# SENSADO.net
KiCad netlist of a schematic drawn in Altium Designer
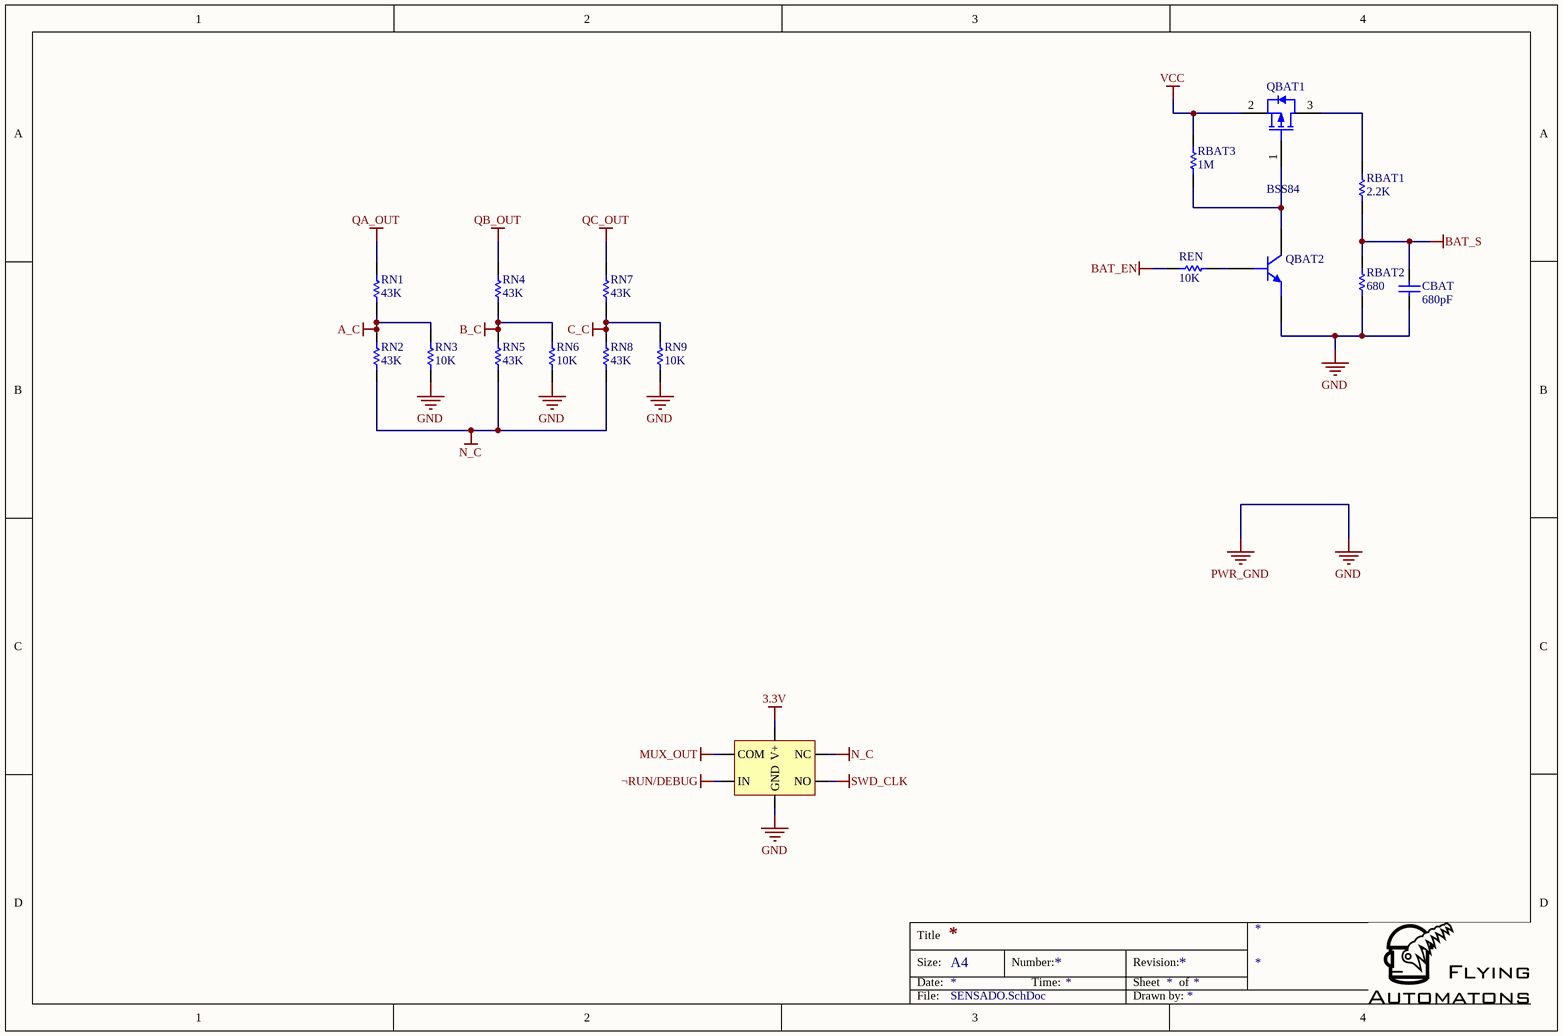
[diagram p0: SENSADO.SchDoc]

(export (version "E")
  (design (tool "Eeschema 10.0.6"))
  (components
    (comp (ref "CBAT")
      (value "680pF")
      (footprint "CAPC1608L")
      (description "CAP CER 680PF 50V 5% NP0 0603")
      (fields
        (field (name "MANUFACTURER") "Samsung Electro-Mechanics America, Inc")
        (field (name "MANUFACTURER PART NUMBER") "CL10C681JB8NFNC")
      )
      (libsource (lib "Passive#csv") (part "CAP_680p_0603_50V_NP0_5%"))
    )
    (comp (ref "mux")
      (value "TS5A3159A")
      (footprint "JEDEC_MO-178AB")
      (description "IC SWITCH SPDT SOT23-6")
      (fields
        (field (name "MANUFACTURER") "\"Texas Instruments\"")
        (field (name "MANUFACTURER PART NUMBER") "TS5A3159ADBVR")
      )
      (libsource (lib "Analog_IC#csv") (part "x-TI_TS5A3159A"))
    )
    (comp (ref "QBAT1")
      (value "BSS84")
      (footprint "SOT23-3L")
      (description "MOSFET P-CH 50V 130MA SOT-23")
      (fields (field (name "MANUFACTURER") "Fairchild Semiconductor"))
      (libsource (lib "Discrete#csv") (part "BSS84"))
    )
    (comp (ref "QBAT2")
      (value "BJT-NPN-BEC")
      (footprint "SOT23-3L")
      (description "TRANSISTOR NPN 40V 0.2A SOT23")
      (fields
        (field (name "MANUFACTURER") "NXP Semiconductors")
        (field (name "MANUFACTURER PART NUMBER") "MMBT3904")
      )
      (libsource (lib "Discrete#csv") (part "MMBT3904"))
    )
    (comp (ref "RBAT1")
      (value "2.2K")
      (footprint "RESC1608L")
      (description "RES 2.2K OHM 1/10W 1% 0603 SMD")
      (fields
        (field (name "MANUFACTURER") "Rohm Semiconductor")
        (field (name "MANUFACTURER PART NUMBER") "MCR03ERTF2201")
      )
      (libsource (lib "Passive#csv") (part "RES_2K2_0603_0W1_1%"))
    )
    (comp (ref "RBAT2")
      (value "680")
      (footprint "RESC1608L")
      (description "RES 680 OHM 1/10W 1% 0603 SMD")
      (fields
        (field (name "MANUFACTURER") "Rohm Semiconductor")
        (field (name "MANUFACTURER PART NUMBER") "MCR03ERTF6800")
      )
      (libsource (lib "Passive#csv") (part "RES_680_0603_0W1_1%"))
    )
    (comp (ref "RBAT3")
      (value "1M")
      (footprint "RESC1608L")
      (description "RES 1.00M OHM 1/10W 1% 0603 SMD")
      (fields
        (field (name "MANUFACTURER") "Yageo")
        (field (name "MANUFACTURER PART NUMBER") "RC0603FR-071ML")
      )
      (libsource (lib "Passive#csv") (part "RES_1M_0603_0W1_1%"))
    )
    (comp (ref "REN")
      (value "10K")
      (footprint "RESC1608L")
      (description "RES 10K OHM 1/10W 5% 0603")
      (fields (field (name "MANUFACTURER PART NUMBER") "RC1608J103CS"))
      (libsource (lib "Passive#csv") (part "RES_10K_0603_0W1_1%"))
    )
    (comp (ref "RN1")
      (value "43K")
      (footprint "RESC1608L")
      (description "RES 10K OHM 1/10W 5% 0603")
      (fields (field (name "MANUFACTURER PART NUMBER") "RC1608J103CS"))
      (libsource (lib "Passive#csv") (part "RES_10K_0603_0W1_1%"))
    )
    (comp (ref "RN2")
      (value "43K")
      (footprint "RESC1608L")
      (description "RES 10K OHM 1/10W 5% 0603")
      (fields (field (name "MANUFACTURER PART NUMBER") "RC1608J103CS"))
      (libsource (lib "Passive#csv") (part "RES_10K_0603_0W1_1%"))
    )
    (comp (ref "RN3")
      (value "10K")
      (footprint "RESC1608L")
      (description "RES 10K OHM 1/10W 5% 0603")
      (fields (field (name "MANUFACTURER PART NUMBER") "RC1608J103CS"))
      (libsource (lib "Passive#csv") (part "RES_10K_0603_0W1_1%"))
    )
    (comp (ref "RN4")
      (value "43K")
      (footprint "RESC1608L")
      (description "RES 10K OHM 1/10W 5% 0603")
      (fields (field (name "MANUFACTURER PART NUMBER") "RC1608J103CS"))
      (libsource (lib "Passive#csv") (part "RES_10K_0603_0W1_1%"))
    )
    (comp (ref "RN5")
      (value "43K")
      (footprint "RESC1608L")
      (description "RES 10K OHM 1/10W 5% 0603")
      (fields (field (name "MANUFACTURER PART NUMBER") "RC1608J103CS"))
      (libsource (lib "Passive#csv") (part "RES_10K_0603_0W1_1%"))
    )
    (comp (ref "RN6")
      (value "10K")
      (footprint "RESC1608L")
      (description "RES 10K OHM 1/10W 5% 0603")
      (fields (field (name "MANUFACTURER PART NUMBER") "RC1608J103CS"))
      (libsource (lib "Passive#csv") (part "RES_10K_0603_0W1_1%"))
    )
    (comp (ref "RN7")
      (value "43K")
      (footprint "RESC1608L")
      (description "RES 10K OHM 1/10W 5% 0603")
      (fields (field (name "MANUFACTURER PART NUMBER") "RC1608J103CS"))
      (libsource (lib "Passive#csv") (part "RES_10K_0603_0W1_1%"))
    )
    (comp (ref "RN8")
      (value "43K")
      (footprint "RESC1608L")
      (description "RES 10K OHM 1/10W 5% 0603")
      (fields (field (name "MANUFACTURER PART NUMBER") "RC1608J103CS"))
      (libsource (lib "Passive#csv") (part "RES_10K_0603_0W1_1%"))
    )
    (comp (ref "RN9")
      (value "10K")
      (footprint "RESC1608L")
      (description "RES 10K OHM 1/10W 5% 0603")
      (fields (field (name "MANUFACTURER PART NUMBER") "RC1608J103CS"))
      (libsource (lib "Passive#csv") (part "RES_10K_0603_0W1_1%"))
    )
  )
  (nets
    (net (code "1") (name "3.3V") (class "Default")
      (node (ref "mux") (pin "5") (pinfunction "V+_5") (pintype "passive"))
    )
    (net (code "2") (name "A_C") (class "Default")
      (node (ref "RN1") (pin "2") (pinfunction "2_2") (pintype "passive"))
      (node (ref "RN2") (pin "1") (pinfunction "1_1") (pintype "passive"))
      (node (ref "RN3") (pin "1") (pinfunction "1_1") (pintype "passive"))
    )
    (net (code "3") (name "BAT_EN") (class "Default")
      (node (ref "REN") (pin "2") (pinfunction "2_2") (pintype "passive"))
    )
    (net (code "4") (name "BAT_S") (class "Default")
      (node (ref "CBAT") (pin "1") (pinfunction "1_1") (pintype "passive"))
      (node (ref "RBAT1") (pin "2") (pinfunction "2_2") (pintype "passive"))
      (node (ref "RBAT2") (pin "1") (pinfunction "1_1") (pintype "passive"))
    )
    (net (code "5") (name "B_C") (class "Default")
      (node (ref "RN4") (pin "2") (pinfunction "2_2") (pintype "passive"))
      (node (ref "RN5") (pin "1") (pinfunction "1_1") (pintype "passive"))
      (node (ref "RN6") (pin "1") (pinfunction "1_1") (pintype "passive"))
    )
    (net (code "6") (name "C_C") (class "Default")
      (node (ref "RN7") (pin "2") (pinfunction "2_2") (pintype "passive"))
      (node (ref "RN8") (pin "1") (pinfunction "1_1") (pintype "passive"))
      (node (ref "RN9") (pin "1") (pinfunction "1_1") (pintype "passive"))
    )
    (net (code "7") (name "GND") (class "Default")
      (node (ref "CBAT") (pin "2") (pinfunction "2_2") (pintype "passive"))
      (node (ref "QBAT2") (pin "2") (pinfunction "E_2") (pintype "passive"))
      (node (ref "RBAT2") (pin "2") (pinfunction "2_2") (pintype "passive"))
      (node (ref "RN3") (pin "2") (pinfunction "2_2") (pintype "passive"))
      (node (ref "RN6") (pin "2") (pinfunction "2_2") (pintype "passive"))
      (node (ref "RN9") (pin "2") (pinfunction "2_2") (pintype "passive"))
      (node (ref "mux") (pin "2") (pinfunction "GND_2") (pintype "passive"))
    )
    (net (code "8") (name "MUX_OUT") (class "Default")
      (node (ref "mux") (pin "4") (pinfunction "COM_4") (pintype "passive"))
    )
    (net (code "9") (name "N_C") (class "Default")
      (node (ref "RN2") (pin "2") (pinfunction "2_2") (pintype "passive"))
      (node (ref "RN5") (pin "2") (pinfunction "2_2") (pintype "passive"))
      (node (ref "RN8") (pin "2") (pinfunction "2_2") (pintype "passive"))
      (node (ref "mux") (pin "3") (pinfunction "NC_3") (pintype "passive"))
    )
    (net (code "10") (name "Net-(QBAT1-D)") (class "Default")
      (node (ref "QBAT1") (pin "3") (pinfunction "D_3") (pintype "passive"))
      (node (ref "RBAT1") (pin "1") (pinfunction "1_1") (pintype "passive"))
    )
    (net (code "11") (name "Net-(QBAT1-G)") (class "Default")
      (node (ref "QBAT1") (pin "1") (pinfunction "G_1") (pintype "passive"))
      (node (ref "QBAT2") (pin "3") (pinfunction "C_3") (pintype "passive"))
      (node (ref "RBAT3") (pin "2") (pinfunction "2_2") (pintype "passive"))
    )
    (net (code "12") (name "Net-(QBAT2-B)") (class "Default")
      (node (ref "QBAT2") (pin "1") (pinfunction "B_1") (pintype "passive"))
      (node (ref "REN") (pin "1") (pinfunction "1_1") (pintype "passive"))
    )
    (net (code "13") (name "QA_OUT") (class "Default")
      (node (ref "RN1") (pin "1") (pinfunction "1_1") (pintype "passive"))
    )
    (net (code "14") (name "QB_OUT") (class "Default")
      (node (ref "RN4") (pin "1") (pinfunction "1_1") (pintype "passive"))
    )
    (net (code "15") (name "QC_OUT") (class "Default")
      (node (ref "RN7") (pin "1") (pinfunction "1_1") (pintype "passive"))
    )
    (net (code "16") (name "SWD_CLK") (class "Default")
      (node (ref "mux") (pin "1") (pinfunction "NO_1") (pintype "passive"))
    )
    (net (code "17") (name "VCC") (class "Default")
      (node (ref "QBAT1") (pin "2") (pinfunction "S_2") (pintype "passive"))
      (node (ref "RBAT3") (pin "1") (pinfunction "1_1") (pintype "passive"))
    )
    (net (code "18") (name "¬RUN{slash}DEBUG") (class "Default")
      (node (ref "mux") (pin "6") (pinfunction "IN_6") (pintype "passive"))
    )
  )
)
